# bue_steuerung.net
KiCad netlist of a schematic drawn in EAGLE
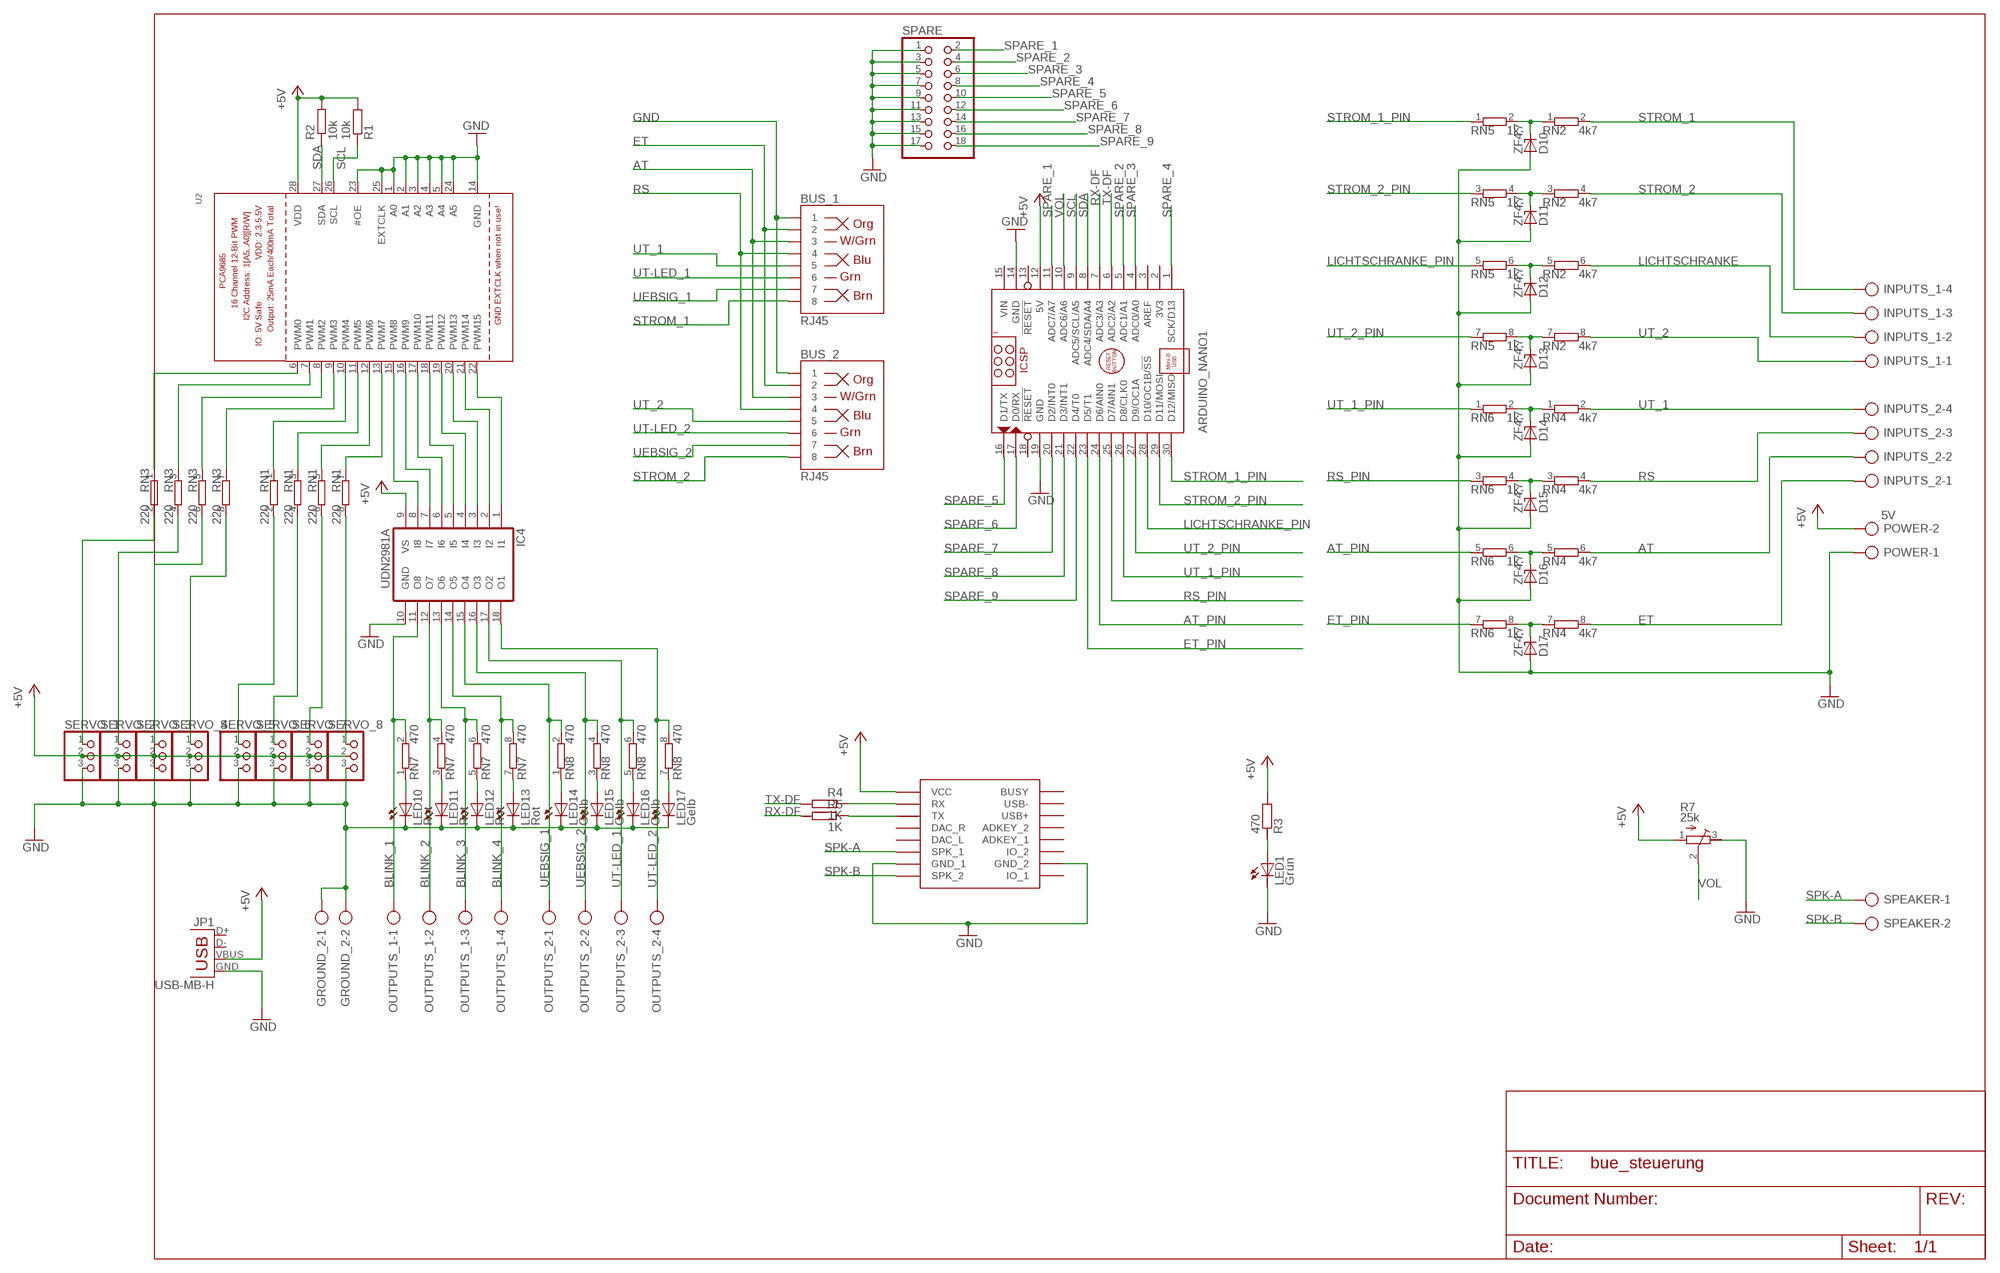
[diagram p0: schematic, sheet 1]

(export (version "E")
  (design (tool "Eeschema 10.0.6"))
  (components
    (comp (ref "ARDUINO_NANO1")
      (value "ARDUINO_NANO")
      (footprint "eagle-import:ARDUINO_NANO")
      (libsource (lib "eagle-import") (part "ARDUINO_NANO"))
    )
    (comp (ref "BUS_1")
      (value "RJ45")
      (footprint "eagle-import:RJ45-8")
      (libsource (lib "eagle-import") (part "RJ45-8PTH"))
    )
    (comp (ref "BUS_2")
      (value "RJ45")
      (footprint "eagle-import:RJ45-8")
      (libsource (lib "eagle-import") (part "RJ45-8PTH"))
    )
    (comp (ref "D10")
      (value "ZF4,7")
      (footprint "eagle-import:ZDIO-2.5")
      (libsource (lib "eagle-import") (part "ZENER-DIODEZD-2.5"))
    )
    (comp (ref "D11")
      (value "ZF4,7")
      (footprint "eagle-import:ZDIO-5")
      (libsource (lib "eagle-import") (part "ZENER-DIODEZD-5"))
    )
    (comp (ref "D12")
      (value "ZF4,7")
      (footprint "eagle-import:ZDIO-10")
      (libsource (lib "eagle-import") (part "ZENER-DIODEZD-10"))
    )
    (comp (ref "D13")
      (value "ZF4,7")
      (footprint "eagle-import:ZDIO12.5")
      (libsource (lib "eagle-import") (part "ZENER-DIODEZD-12.5"))
    )
    (comp (ref "D14")
      (value "ZF4,7")
      (footprint "eagle-import:ZDIO12.5")
      (libsource (lib "eagle-import") (part "ZENER-DIODEZD-12.5"))
    )
    (comp (ref "D15")
      (value "ZF4,7")
      (footprint "eagle-import:ZDIO-10")
      (libsource (lib "eagle-import") (part "ZENER-DIODEZD-10"))
    )
    (comp (ref "D16")
      (value "ZF4,7")
      (footprint "eagle-import:ZDIO-5")
      (libsource (lib "eagle-import") (part "ZENER-DIODEZD-5"))
    )
    (comp (ref "D17")
      (value "ZF4,7")
      (footprint "eagle-import:ZDIO-2.5")
      (libsource (lib "eagle-import") (part "ZENER-DIODEZD-2.5"))
    )
    (comp (ref "GROUND_2")
      (value "AK500/2")
      (footprint "eagle-import:AK500_2")
      (libsource (lib "eagle-import") (part "AK500/2"))
    )
    (comp (ref "IC4")
      (value "UDN2981A")
      (footprint "eagle-import:DIL18")
      (libsource (lib "eagle-import") (part "UDN298A1"))
    )
    (comp (ref "INPUTS_1")
      (value "AK500/4")
      (footprint "eagle-import:AK500_4")
      (libsource (lib "eagle-import") (part "AK500/4"))
    )
    (comp (ref "INPUTS_2")
      (value "AK500/4")
      (footprint "eagle-import:AK500_4")
      (libsource (lib "eagle-import") (part "AK500/4"))
    )
    (comp (ref "JP1")
      (value "USB-MB-H")
      (footprint "eagle-import:USB-MB-H")
      (libsource (lib "eagle-import") (part "USB-MB-H"))
    )
    (comp (ref "LED1")
      (value "Grün")
      (footprint "eagle-import:LED3MM")
      (libsource (lib "eagle-import") (part "LED3MM"))
    )
    (comp (ref "LED10")
      (value "Rot")
      (footprint "eagle-import:LED3MM")
      (libsource (lib "eagle-import") (part "LED3MM"))
    )
    (comp (ref "LED11")
      (value "Rot")
      (footprint "eagle-import:LED3MM")
      (libsource (lib "eagle-import") (part "LED3MM"))
    )
    (comp (ref "LED12")
      (value "Rot")
      (footprint "eagle-import:LED3MM")
      (libsource (lib "eagle-import") (part "LED3MM"))
    )
    (comp (ref "LED13")
      (value "Rot")
      (footprint "eagle-import:LED3MM")
      (libsource (lib "eagle-import") (part "LED3MM"))
    )
    (comp (ref "LED14")
      (value "Gelb")
      (footprint "eagle-import:LED3MM")
      (libsource (lib "eagle-import") (part "LED3MM"))
    )
    (comp (ref "LED15")
      (value "Gelb")
      (footprint "eagle-import:LED3MM")
      (libsource (lib "eagle-import") (part "LED3MM"))
    )
    (comp (ref "LED16")
      (value "Gelb")
      (footprint "eagle-import:LED3MM")
      (libsource (lib "eagle-import") (part "LED3MM"))
    )
    (comp (ref "LED17")
      (value "Gelb")
      (footprint "eagle-import:LED3MM")
      (libsource (lib "eagle-import") (part "LED3MM"))
    )
    (comp (ref "OUTPUTS_1")
      (value "AK500/4")
      (footprint "eagle-import:AK500_4")
      (libsource (lib "eagle-import") (part "AK500/4"))
    )
    (comp (ref "OUTPUTS_2")
      (value "AK500/4")
      (footprint "eagle-import:AK500_4")
      (libsource (lib "eagle-import") (part "AK500/4"))
    )
    (comp (ref "POWER")
      (value "5V")
      (footprint "eagle-import:AK500_2")
      (libsource (lib "eagle-import") (part "AK500/2"))
    )
    (comp (ref "R1")
      (value "10k")
      (footprint "eagle-import:0207_10")
      (libsource (lib "eagle-import") (part "R-EU_0207/10"))
    )
    (comp (ref "R2")
      (value "10k")
      (footprint "eagle-import:0207_10")
      (libsource (lib "eagle-import") (part "R-EU_0207/10"))
    )
    (comp (ref "R3")
      (value "470")
      (footprint "eagle-import:0207_10")
      (libsource (lib "eagle-import") (part "R-EU_0207/10"))
    )
    (comp (ref "R4")
      (value "1K")
      (footprint "eagle-import:0207_10")
      (libsource (lib "eagle-import") (part "R-EU_0207/10"))
    )
    (comp (ref "R5")
      (value "1K")
      (footprint "eagle-import:0207_10")
      (libsource (lib "eagle-import") (part "R-EU_0207/10"))
    )
    (comp (ref "R7")
      (value "25k")
      (footprint "eagle-import:RTRIM64Z")
      (libsource (lib "eagle-import") (part "R-TRIMM64Z"))
    )
    (comp (ref "RN1")
      (value "220")
      (footprint "eagle-import:SIL8")
      (libsource (lib "eagle-import") (part "E4RP"))
    )
    (comp (ref "RN2")
      (value "4k7")
      (footprint "eagle-import:SIL8")
      (libsource (lib "eagle-import") (part "E4RP"))
    )
    (comp (ref "RN3")
      (value "220")
      (footprint "eagle-import:SIL8")
      (libsource (lib "eagle-import") (part "E4RP"))
    )
    (comp (ref "RN4")
      (value "4k7")
      (footprint "eagle-import:SIL8")
      (libsource (lib "eagle-import") (part "E4RP"))
    )
    (comp (ref "RN5")
      (value "1k")
      (footprint "eagle-import:SIL8")
      (libsource (lib "eagle-import") (part "E4RP"))
    )
    (comp (ref "RN6")
      (value "1k")
      (footprint "eagle-import:SIL8")
      (libsource (lib "eagle-import") (part "E4RP"))
    )
    (comp (ref "RN7")
      (value "470")
      (footprint "eagle-import:SIL8")
      (libsource (lib "eagle-import") (part "E4RP"))
    )
    (comp (ref "RN8")
      (value "470")
      (footprint "eagle-import:SIL8")
      (libsource (lib "eagle-import") (part "E4RP"))
    )
    (comp (ref "SERVO_1")
      (value "PINHD-1X3")
      (footprint "eagle-import:1X03")
      (libsource (lib "eagle-import") (part "PINHD-1X3"))
    )
    (comp (ref "SERVO_2")
      (value "PINHD-1X3")
      (footprint "eagle-import:1X03")
      (libsource (lib "eagle-import") (part "PINHD-1X3"))
    )
    (comp (ref "SERVO_3")
      (value "PINHD-1X3")
      (footprint "eagle-import:1X03")
      (libsource (lib "eagle-import") (part "PINHD-1X3"))
    )
    (comp (ref "SERVO_4")
      (value "PINHD-1X3")
      (footprint "eagle-import:1X03")
      (libsource (lib "eagle-import") (part "PINHD-1X3"))
    )
    (comp (ref "SERVO_5")
      (value "PINHD-1X3")
      (footprint "eagle-import:1X03")
      (libsource (lib "eagle-import") (part "PINHD-1X3"))
    )
    (comp (ref "SERVO_6")
      (value "PINHD-1X3")
      (footprint "eagle-import:1X03")
      (libsource (lib "eagle-import") (part "PINHD-1X3"))
    )
    (comp (ref "SERVO_7")
      (value "PINHD-1X3")
      (footprint "eagle-import:1X03")
      (libsource (lib "eagle-import") (part "PINHD-1X3"))
    )
    (comp (ref "SERVO_8")
      (value "PINHD-1X3")
      (footprint "eagle-import:1X03")
      (libsource (lib "eagle-import") (part "PINHD-1X3"))
    )
    (comp (ref "SPARE")
      (value "PINHD-2X9")
      (footprint "eagle-import:2X09")
      (libsource (lib "eagle-import") (part "PINHD-2X9"))
    )
    (comp (ref "SPEAKER")
      (value "AK500/2")
      (footprint "eagle-import:AK500_2")
      (libsource (lib "eagle-import") (part "AK500/2"))
    )
    (comp (ref "U$1")
      (value "DFPLAYER")
      (footprint "eagle-import:DFPLAYER")
      (libsource (lib "eagle-import") (part "DFPLAYER"))
    )
    (comp (ref "U2")
      (value "PCA9685")
      (footprint "eagle-import:TSSOP28")
      (libsource (lib "eagle-import") (part "PCA9685"))
    )
  )
  (nets
    (net (code "1") (name "+5V") (class "Default")
      (node (ref "ARDUINO_NANO1") (pin "12") (pinfunction "5V_12") (pintype "power_in"))
      (node (ref "IC4") (pin "9") (pinfunction "VS_9") (pintype "passive"))
      (node (ref "JP1") (pin "VBUS") (pinfunction "VBUS_VBUS") (pintype "bidirectional"))
      (node (ref "POWER") (pin "2") (pinfunction "KL_2") (pintype "passive"))
      (node (ref "R1") (pin "2") (pinfunction "2_2") (pintype "passive"))
      (node (ref "R2") (pin "2") (pinfunction "2_2") (pintype "passive"))
      (node (ref "R3") (pin "2") (pinfunction "2_2") (pintype "passive"))
      (node (ref "R7") (pin "1") (pinfunction "E_1") (pintype "passive"))
      (node (ref "SERVO_1") (pin "2") (pinfunction "2_2") (pintype "passive"))
      (node (ref "SERVO_2") (pin "2") (pinfunction "2_2") (pintype "passive"))
      (node (ref "SERVO_3") (pin "2") (pinfunction "2_2") (pintype "passive"))
      (node (ref "SERVO_4") (pin "2") (pinfunction "2_2") (pintype "passive"))
      (node (ref "SERVO_5") (pin "2") (pinfunction "2_2") (pintype "passive"))
      (node (ref "SERVO_6") (pin "2") (pinfunction "2_2") (pintype "passive"))
      (node (ref "SERVO_7") (pin "2") (pinfunction "2_2") (pintype "passive"))
      (node (ref "SERVO_8") (pin "2") (pinfunction "2_2") (pintype "passive"))
      (node (ref "U$1") (pin "VCC") (pinfunction "VCC_VCC") (pintype "bidirectional"))
      (node (ref "U2") (pin "28") (pinfunction "VDD_28") (pintype "power_in"))
    )
    (net (code "2") (name "/AT") (class "Default")
      (node (ref "BUS_1") (pin "3") (pinfunction "3_3") (pintype "bidirectional"))
      (node (ref "BUS_2") (pin "3") (pinfunction "3_3") (pintype "bidirectional"))
      (node (ref "INPUTS_2") (pin "2") (pinfunction "KL_2") (pintype "passive"))
      (node (ref "RN4") (pin "6") (pinfunction "2_6") (pintype "passive"))
    )
    (net (code "3") (name "/AT_PIN") (class "Default")
      (node (ref "ARDUINO_NANO1") (pin "24") (pinfunction "D6/AIN0_24") (pintype "bidirectional"))
      (node (ref "RN6") (pin "5") (pinfunction "1_5") (pintype "passive"))
    )
    (net (code "4") (name "/BLINK_1") (class "Default")
      (node (ref "IC4") (pin "11") (pinfunction "O8_11") (pintype "open_collector"))
      (node (ref "OUTPUTS_1") (pin "1") (pinfunction "KL_1") (pintype "passive"))
      (node (ref "RN7") (pin "2") (pinfunction "2_2") (pintype "passive"))
    )
    (net (code "5") (name "/BLINK_2") (class "Default")
      (node (ref "IC4") (pin "12") (pinfunction "O7_12") (pintype "open_collector"))
      (node (ref "OUTPUTS_1") (pin "2") (pinfunction "KL_2") (pintype "passive"))
      (node (ref "RN7") (pin "4") (pinfunction "2_4") (pintype "passive"))
    )
    (net (code "6") (name "/BLINK_3") (class "Default")
      (node (ref "IC4") (pin "13") (pinfunction "O6_13") (pintype "open_collector"))
      (node (ref "OUTPUTS_1") (pin "3") (pinfunction "KL_3") (pintype "passive"))
      (node (ref "RN7") (pin "6") (pinfunction "2_6") (pintype "passive"))
    )
    (net (code "7") (name "/BLINK_4") (class "Default")
      (node (ref "IC4") (pin "14") (pinfunction "O5_14") (pintype "open_collector"))
      (node (ref "OUTPUTS_1") (pin "4") (pinfunction "KL_4") (pintype "passive"))
      (node (ref "RN7") (pin "8") (pinfunction "2_8") (pintype "passive"))
    )
    (net (code "8") (name "/ET") (class "Default")
      (node (ref "BUS_1") (pin "2") (pinfunction "2_2") (pintype "bidirectional"))
      (node (ref "BUS_2") (pin "2") (pinfunction "2_2") (pintype "bidirectional"))
      (node (ref "INPUTS_2") (pin "1") (pinfunction "KL_1") (pintype "passive"))
      (node (ref "RN4") (pin "8") (pinfunction "2_8") (pintype "passive"))
    )
    (net (code "9") (name "/ET_PIN") (class "Default")
      (node (ref "ARDUINO_NANO1") (pin "23") (pinfunction "D5/T1_23") (pintype "bidirectional"))
      (node (ref "RN6") (pin "7") (pinfunction "1_7") (pintype "passive"))
    )
    (net (code "10") (name "/LICHTSCHRANKE") (class "Default")
      (node (ref "INPUTS_1") (pin "2") (pinfunction "KL_2") (pintype "passive"))
      (node (ref "RN2") (pin "6") (pinfunction "2_6") (pintype "passive"))
    )
    (net (code "11") (name "/LICHTSCHRANKE_PIN") (class "Default")
      (node (ref "ARDUINO_NANO1") (pin "28") (pinfunction "D10/OC1B/~{SS}_28") (pintype "bidirectional"))
      (node (ref "RN5") (pin "5") (pinfunction "1_5") (pintype "passive"))
    )
    (net (code "12") (name "/RS") (class "Default")
      (node (ref "BUS_1") (pin "4") (pinfunction "4_4") (pintype "bidirectional"))
      (node (ref "BUS_2") (pin "4") (pinfunction "4_4") (pintype "bidirectional"))
      (node (ref "INPUTS_2") (pin "3") (pinfunction "KL_3") (pintype "passive"))
      (node (ref "RN4") (pin "4") (pinfunction "2_4") (pintype "passive"))
    )
    (net (code "13") (name "/RS_PIN") (class "Default")
      (node (ref "ARDUINO_NANO1") (pin "25") (pinfunction "D7/AIN1_25") (pintype "bidirectional"))
      (node (ref "RN6") (pin "3") (pinfunction "1_3") (pintype "passive"))
    )
    (net (code "14") (name "/RX-DF") (class "Default")
      (node (ref "ARDUINO_NANO1") (pin "7") (pinfunction "ADC3/A3_7") (pintype "bidirectional"))
      (node (ref "R5") (pin "2") (pinfunction "2_2") (pintype "passive"))
    )
    (net (code "15") (name "/SCL") (class "Default")
      (node (ref "ARDUINO_NANO1") (pin "9") (pinfunction "ADC5/SCL/A5_9") (pintype "bidirectional"))
      (node (ref "R1") (pin "1") (pinfunction "1_1") (pintype "passive"))
      (node (ref "U2") (pin "26") (pinfunction "SCL_26") (pintype "bidirectional"))
    )
    (net (code "16") (name "/SDA") (class "Default")
      (node (ref "ARDUINO_NANO1") (pin "8") (pinfunction "ADC4/SDA/A4_8") (pintype "bidirectional"))
      (node (ref "R2") (pin "1") (pinfunction "1_1") (pintype "passive"))
      (node (ref "U2") (pin "27") (pinfunction "SDA_27") (pintype "bidirectional"))
    )
    (net (code "17") (name "/SPARE_1") (class "Default")
      (node (ref "ARDUINO_NANO1") (pin "11") (pinfunction "ADC7/A7_11") (pintype "bidirectional"))
      (node (ref "SPARE") (pin "2") (pinfunction "2_2") (pintype "passive"))
    )
    (net (code "18") (name "/SPARE_2") (class "Default")
      (node (ref "ARDUINO_NANO1") (pin "5") (pinfunction "ADC1/A1_5") (pintype "bidirectional"))
      (node (ref "SPARE") (pin "4") (pinfunction "4_4") (pintype "passive"))
    )
    (net (code "19") (name "/SPARE_3") (class "Default")
      (node (ref "ARDUINO_NANO1") (pin "4") (pinfunction "ADC0/A0_4") (pintype "bidirectional"))
      (node (ref "SPARE") (pin "6") (pinfunction "6_6") (pintype "passive"))
    )
    (net (code "20") (name "/SPARE_4") (class "Default")
      (node (ref "ARDUINO_NANO1") (pin "1") (pinfunction "SCK/D13_1") (pintype "bidirectional"))
      (node (ref "SPARE") (pin "8") (pinfunction "8_8") (pintype "passive"))
    )
    (net (code "21") (name "/SPARE_5") (class "Default")
      (node (ref "ARDUINO_NANO1") (pin "16") (pinfunction "D1/TX_16") (pintype "bidirectional"))
      (node (ref "SPARE") (pin "10") (pinfunction "10_10") (pintype "passive"))
    )
    (net (code "22") (name "/SPARE_6") (class "Default")
      (node (ref "ARDUINO_NANO1") (pin "17") (pinfunction "D0/RX_17") (pintype "bidirectional"))
      (node (ref "SPARE") (pin "12") (pinfunction "12_12") (pintype "passive"))
    )
    (net (code "23") (name "/SPARE_7") (class "Default")
      (node (ref "ARDUINO_NANO1") (pin "20") (pinfunction "D2/INT0_20") (pintype "bidirectional"))
      (node (ref "SPARE") (pin "14") (pinfunction "14_14") (pintype "passive"))
    )
    (net (code "24") (name "/SPARE_8") (class "Default")
      (node (ref "ARDUINO_NANO1") (pin "21") (pinfunction "D3/INT1_21") (pintype "bidirectional"))
      (node (ref "SPARE") (pin "16") (pinfunction "16_16") (pintype "passive"))
    )
    (net (code "25") (name "/SPARE_9") (class "Default")
      (node (ref "ARDUINO_NANO1") (pin "22") (pinfunction "D4/T0_22") (pintype "bidirectional"))
      (node (ref "SPARE") (pin "18") (pinfunction "18_18") (pintype "passive"))
    )
    (net (code "26") (name "/SPK-A") (class "Default")
      (node (ref "SPEAKER") (pin "1") (pinfunction "KL_1") (pintype "passive"))
      (node (ref "U$1") (pin "SPK1") (pinfunction "SPK_1_SPK1") (pintype "bidirectional"))
    )
    (net (code "27") (name "/SPK-B") (class "Default")
      (node (ref "SPEAKER") (pin "2") (pinfunction "KL_2") (pintype "passive"))
      (node (ref "U$1") (pin "SPK2") (pinfunction "SPK_2_SPK2") (pintype "bidirectional"))
    )
    (net (code "28") (name "/STROM_1") (class "Default")
      (node (ref "BUS_1") (pin "8") (pinfunction "8_8") (pintype "bidirectional"))
      (node (ref "INPUTS_1") (pin "4") (pinfunction "KL_4") (pintype "passive"))
      (node (ref "RN2") (pin "2") (pinfunction "2_2") (pintype "passive"))
    )
    (net (code "29") (name "/STROM_1_PIN") (class "Default")
      (node (ref "ARDUINO_NANO1") (pin "30") (pinfunction "D12/MISO_30") (pintype "bidirectional"))
      (node (ref "RN5") (pin "1") (pinfunction "1_1") (pintype "passive"))
    )
    (net (code "30") (name "/STROM_2") (class "Default")
      (node (ref "BUS_2") (pin "8") (pinfunction "8_8") (pintype "bidirectional"))
      (node (ref "INPUTS_1") (pin "3") (pinfunction "KL_3") (pintype "passive"))
      (node (ref "RN2") (pin "4") (pinfunction "2_4") (pintype "passive"))
    )
    (net (code "31") (name "/STROM_2_PIN") (class "Default")
      (node (ref "ARDUINO_NANO1") (pin "29") (pinfunction "D11/MOSI_29") (pintype "bidirectional"))
      (node (ref "RN5") (pin "3") (pinfunction "1_3") (pintype "passive"))
    )
    (net (code "32") (name "/TX-DF") (class "Default")
      (node (ref "ARDUINO_NANO1") (pin "6") (pinfunction "ADC2/A2_6") (pintype "bidirectional"))
      (node (ref "R4") (pin "2") (pinfunction "2_2") (pintype "passive"))
    )
    (net (code "33") (name "/UEBSIG_1") (class "Default")
      (node (ref "BUS_1") (pin "7") (pinfunction "7_7") (pintype "bidirectional"))
      (node (ref "IC4") (pin "15") (pinfunction "O4_15") (pintype "open_collector"))
      (node (ref "OUTPUTS_2") (pin "1") (pinfunction "KL_1") (pintype "passive"))
      (node (ref "RN8") (pin "2") (pinfunction "2_2") (pintype "passive"))
    )
    (net (code "34") (name "/UEBSIG_2") (class "Default")
      (node (ref "BUS_2") (pin "7") (pinfunction "7_7") (pintype "bidirectional"))
      (node (ref "IC4") (pin "16") (pinfunction "O3_16") (pintype "open_collector"))
      (node (ref "OUTPUTS_2") (pin "2") (pinfunction "KL_2") (pintype "passive"))
      (node (ref "RN8") (pin "4") (pinfunction "2_4") (pintype "passive"))
    )
    (net (code "35") (name "/UT-LED_1") (class "Default")
      (node (ref "BUS_1") (pin "6") (pinfunction "6_6") (pintype "bidirectional"))
      (node (ref "IC4") (pin "17") (pinfunction "O2_17") (pintype "open_collector"))
      (node (ref "OUTPUTS_2") (pin "3") (pinfunction "KL_3") (pintype "passive"))
      (node (ref "RN8") (pin "6") (pinfunction "2_6") (pintype "passive"))
    )
    (net (code "36") (name "/UT-LED_2") (class "Default")
      (node (ref "BUS_2") (pin "6") (pinfunction "6_6") (pintype "bidirectional"))
      (node (ref "IC4") (pin "18") (pinfunction "O1_18") (pintype "open_collector"))
      (node (ref "OUTPUTS_2") (pin "4") (pinfunction "KL_4") (pintype "passive"))
      (node (ref "RN8") (pin "8") (pinfunction "2_8") (pintype "passive"))
    )
    (net (code "37") (name "/UT_1") (class "Default")
      (node (ref "BUS_1") (pin "5") (pinfunction "5_5") (pintype "bidirectional"))
      (node (ref "INPUTS_2") (pin "4") (pinfunction "KL_4") (pintype "passive"))
      (node (ref "RN4") (pin "2") (pinfunction "2_2") (pintype "passive"))
    )
    (net (code "38") (name "/UT_1_PIN") (class "Default")
      (node (ref "ARDUINO_NANO1") (pin "26") (pinfunction "D8/CLK0_26") (pintype "bidirectional"))
      (node (ref "RN6") (pin "1") (pinfunction "1_1") (pintype "passive"))
    )
    (net (code "39") (name "/UT_2") (class "Default")
      (node (ref "BUS_2") (pin "5") (pinfunction "5_5") (pintype "bidirectional"))
      (node (ref "INPUTS_1") (pin "1") (pinfunction "KL_1") (pintype "passive"))
      (node (ref "RN2") (pin "8") (pinfunction "2_8") (pintype "passive"))
    )
    (net (code "40") (name "/UT_2_PIN") (class "Default")
      (node (ref "ARDUINO_NANO1") (pin "27") (pinfunction "D9/OC1A_27") (pintype "bidirectional"))
      (node (ref "RN5") (pin "7") (pinfunction "1_7") (pintype "passive"))
    )
    (net (code "41") (name "/VIN") (class "Default")
      (node (ref "ARDUINO_NANO1") (pin "15") (pinfunction "VIN_15") (pintype "power_in"))
    )
    (net (code "42") (name "/VOL") (class "Default")
      (node (ref "ARDUINO_NANO1") (pin "10") (pinfunction "ADC6/A6_10") (pintype "bidirectional"))
      (node (ref "R7") (pin "2") (pinfunction "S_2") (pintype "passive"))
    )
    (net (code "43") (name "GND") (class "Default")
      (node (ref "ARDUINO_NANO1") (pin "14") (pinfunction "GND_14") (pintype "power_in"))
      (node (ref "ARDUINO_NANO1") (pin "19") (pinfunction "GND_19") (pintype "power_in"))
      (node (ref "BUS_1") (pin "1") (pinfunction "1_1") (pintype "bidirectional"))
      (node (ref "BUS_2") (pin "1") (pinfunction "1_1") (pintype "bidirectional"))
      (node (ref "D10") (pin "A") (pinfunction "A_A") (pintype "passive"))
      (node (ref "D11") (pin "A") (pinfunction "A_A") (pintype "passive"))
      (node (ref "D12") (pin "A") (pinfunction "A_A") (pintype "passive"))
      (node (ref "D13") (pin "A") (pinfunction "A_A") (pintype "passive"))
      (node (ref "D14") (pin "A") (pinfunction "A_A") (pintype "passive"))
      (node (ref "D15") (pin "A") (pinfunction "A_A") (pintype "passive"))
      (node (ref "D16") (pin "A") (pinfunction "A_A") (pintype "passive"))
      (node (ref "D17") (pin "A") (pinfunction "A_A") (pintype "passive"))
      (node (ref "GROUND_2") (pin "1") (pinfunction "KL_1") (pintype "passive"))
      (node (ref "GROUND_2") (pin "2") (pinfunction "KL_2") (pintype "passive"))
      (node (ref "IC4") (pin "10") (pinfunction "GND_10") (pintype "power_in"))
      (node (ref "JP1") (pin "GND") (pinfunction "GND_GND") (pintype "bidirectional"))
      (node (ref "LED1") (pin "K") (pinfunction "C_K") (pintype "passive"))
      (node (ref "LED10") (pin "K") (pinfunction "C_K") (pintype "passive"))
      (node (ref "LED11") (pin "K") (pinfunction "C_K") (pintype "passive"))
      (node (ref "LED12") (pin "K") (pinfunction "C_K") (pintype "passive"))
      (node (ref "LED13") (pin "K") (pinfunction "C_K") (pintype "passive"))
      (node (ref "LED14") (pin "K") (pinfunction "C_K") (pintype "passive"))
      (node (ref "LED15") (pin "K") (pinfunction "C_K") (pintype "passive"))
      (node (ref "LED16") (pin "K") (pinfunction "C_K") (pintype "passive"))
      (node (ref "LED17") (pin "K") (pinfunction "C_K") (pintype "passive"))
      (node (ref "POWER") (pin "1") (pinfunction "KL_1") (pintype "passive"))
      (node (ref "R7") (pin "3") (pinfunction "A_3") (pintype "passive"))
      (node (ref "SERVO_1") (pin "3") (pinfunction "3_3") (pintype "passive"))
      (node (ref "SERVO_2") (pin "3") (pinfunction "3_3") (pintype "passive"))
      (node (ref "SERVO_3") (pin "3") (pinfunction "3_3") (pintype "passive"))
      (node (ref "SERVO_4") (pin "3") (pinfunction "3_3") (pintype "passive"))
      (node (ref "SERVO_5") (pin "3") (pinfunction "3_3") (pintype "passive"))
      (node (ref "SERVO_6") (pin "3") (pinfunction "3_3") (pintype "passive"))
      (node (ref "SERVO_7") (pin "3") (pinfunction "3_3") (pintype "passive"))
      (node (ref "SERVO_8") (pin "3") (pinfunction "3_3") (pintype "passive"))
      (node (ref "SPARE") (pin "1") (pinfunction "1_1") (pintype "passive"))
      (node (ref "SPARE") (pin "11") (pinfunction "11_11") (pintype "passive"))
      (node (ref "SPARE") (pin "13") (pinfunction "13_13") (pintype "passive"))
      (node (ref "SPARE") (pin "15") (pinfunction "15_15") (pintype "passive"))
      (node (ref "SPARE") (pin "17") (pinfunction "17_17") (pintype "passive"))
      (node (ref "SPARE") (pin "3") (pinfunction "3_3") (pintype "passive"))
      (node (ref "SPARE") (pin "5") (pinfunction "5_5") (pintype "passive"))
      (node (ref "SPARE") (pin "7") (pinfunction "7_7") (pintype "passive"))
      (node (ref "SPARE") (pin "9") (pinfunction "9_9") (pintype "passive"))
      (node (ref "U$1") (pin "GND_1") (pinfunction "GND_1_GND_1") (pintype "bidirectional"))
      (node (ref "U$1") (pin "GND_2") (pinfunction "GND_2_GND_2") (pintype "bidirectional"))
      (node (ref "U2") (pin "1") (pinfunction "A0_1") (pintype "bidirectional"))
      (node (ref "U2") (pin "14") (pinfunction "GND_14") (pintype "power_in"))
      (node (ref "U2") (pin "2") (pinfunction "A1_2") (pintype "bidirectional"))
      (node (ref "U2") (pin "23") (pinfunction "#OE_23") (pintype "input"))
      (node (ref "U2") (pin "24") (pinfunction "A5_24") (pintype "bidirectional"))
      (node (ref "U2") (pin "25") (pinfunction "EXTCLK_25") (pintype "input"))
      (node (ref "U2") (pin "3") (pinfunction "A2_3") (pintype "bidirectional"))
      (node (ref "U2") (pin "4") (pinfunction "A3_4") (pintype "bidirectional"))
      (node (ref "U2") (pin "5") (pinfunction "A4_5") (pintype "bidirectional"))
    )
    (net (code "44") (name "Net-(D10-PadC)") (class "Default")
      (node (ref "D10") (pin "C") (pinfunction "C_C") (pintype "passive"))
      (node (ref "RN2") (pin "1") (pinfunction "1_1") (pintype "passive"))
      (node (ref "RN5") (pin "2") (pinfunction "2_2") (pintype "passive"))
    )
    (net (code "45") (name "Net-(D14-PadC)") (class "Default")
      (node (ref "D14") (pin "C") (pinfunction "C_C") (pintype "passive"))
      (node (ref "RN4") (pin "1") (pinfunction "1_1") (pintype "passive"))
      (node (ref "RN6") (pin "2") (pinfunction "2_2") (pintype "passive"))
    )
    (net (code "46") (name "Net-(IC4-I1)") (class "Default")
      (node (ref "IC4") (pin "1") (pinfunction "I1_1") (pintype "input"))
      (node (ref "U2") (pin "22") (pinfunction "PWM15_22") (pintype "output"))
    )
    (net (code "47") (name "Net-(IC4-I2)") (class "Default")
      (node (ref "IC4") (pin "2") (pinfunction "I2_2") (pintype "input"))
      (node (ref "U2") (pin "21") (pinfunction "PWM14_21") (pintype "output"))
    )
    (net (code "48") (name "Net-(IC4-I3)") (class "Default")
      (node (ref "IC4") (pin "3") (pinfunction "I3_3") (pintype "input"))
      (node (ref "U2") (pin "20") (pinfunction "PWM13_20") (pintype "output"))
    )
    (net (code "49") (name "Net-(IC4-I4)") (class "Default")
      (node (ref "IC4") (pin "4") (pinfunction "I4_4") (pintype "input"))
      (node (ref "U2") (pin "19") (pinfunction "PWM12_19") (pintype "output"))
    )
    (net (code "50") (name "Net-(IC4-I5)") (class "Default")
      (node (ref "IC4") (pin "5") (pinfunction "I5_5") (pintype "input"))
      (node (ref "U2") (pin "18") (pinfunction "PWM11_18") (pintype "output"))
    )
    (net (code "51") (name "Net-(IC4-I6)") (class "Default")
      (node (ref "IC4") (pin "6") (pinfunction "I6_6") (pintype "input"))
      (node (ref "U2") (pin "17") (pinfunction "PWM10_17") (pintype "output"))
    )
    (net (code "52") (name "Net-(IC4-I7)") (class "Default")
      (node (ref "IC4") (pin "7") (pinfunction "I7_7") (pintype "input"))
      (node (ref "U2") (pin "16") (pinfunction "PWM9_16") (pintype "output"))
    )
    (net (code "53") (name "Net-(IC4-I8)") (class "Default")
      (node (ref "IC4") (pin "8") (pinfunction "I8_8") (pintype "input"))
      (node (ref "U2") (pin "15") (pinfunction "PWM8_15") (pintype "output"))
    )
    (net (code "54") (name "Net-(LED1-PadA)") (class "Default")
      (node (ref "LED1") (pin "A") (pinfunction "A_A") (pintype "passive"))
      (node (ref "R3") (pin "1") (pinfunction "1_1") (pintype "passive"))
    )
    (net (code "55") (name "Net-(LED10-PadA)") (class "Default")
      (node (ref "LED10") (pin "A") (pinfunction "A_A") (pintype "passive"))
      (node (ref "RN7") (pin "1") (pinfunction "1_1") (pintype "passive"))
    )
    (net (code "56") (name "Net-(LED14-PadA)") (class "Default")
      (node (ref "LED14") (pin "A") (pinfunction "A_A") (pintype "passive"))
      (node (ref "RN8") (pin "1") (pinfunction "1_1") (pintype "passive"))
    )
    (net (code "57") (name "Net-(R4-Pad1)") (class "Default")
      (node (ref "R4") (pin "1") (pinfunction "1_1") (pintype "passive"))
      (node (ref "U$1") (pin "RX") (pinfunction "RX_RX") (pintype "bidirectional"))
    )
    (net (code "58") (name "Net-(R5-Pad1)") (class "Default")
      (node (ref "R5") (pin "1") (pinfunction "1_1") (pintype "passive"))
      (node (ref "U$1") (pin "TX") (pinfunction "TX_TX") (pintype "bidirectional"))
    )
    (net (code "59") (name "Net-(RN1-Pad2)") (class "Default")
      (node (ref "RN1") (pin "2") (pinfunction "2_2") (pintype "passive"))
      (node (ref "SERVO_5") (pin "1") (pinfunction "1_1") (pintype "passive"))
    )
    (net (code "60") (name "Net-(RN1B-1)") (class "Default")
      (node (ref "RN1") (pin "3") (pinfunction "1_3") (pintype "passive"))
      (node (ref "U2") (pin "11") (pinfunction "PWM5_11") (pintype "output"))
    )
    (net (code "61") (name "Net-(RN1B-2)") (class "Default")
      (node (ref "RN1") (pin "4") (pinfunction "2_4") (pintype "passive"))
      (node (ref "SERVO_6") (pin "1") (pinfunction "1_1") (pintype "passive"))
    )
    (net (code "62") (name "Net-(RN1C-1)") (class "Default")
      (node (ref "RN1") (pin "5") (pinfunction "1_5") (pintype "passive"))
      (node (ref "U2") (pin "12") (pinfunction "PWM6_12") (pintype "output"))
    )
    (net (code "63") (name "Net-(RN1C-2)") (class "Default")
      (node (ref "RN1") (pin "6") (pinfunction "2_6") (pintype "passive"))
      (node (ref "SERVO_7") (pin "1") (pinfunction "1_1") (pintype "passive"))
    )
    (net (code "64") (name "Net-(RN1D-1)") (class "Default")
      (node (ref "RN1") (pin "7") (pinfunction "1_7") (pintype "passive"))
      (node (ref "U2") (pin "13") (pinfunction "PWM7_13") (pintype "output"))
    )
    (net (code "65") (name "Net-(RN1D-2)") (class "Default")
      (node (ref "RN1") (pin "8") (pinfunction "2_8") (pintype "passive"))
      (node (ref "SERVO_8") (pin "1") (pinfunction "1_1") (pintype "passive"))
    )
    (net (code "66") (name "Net-(RN2B-1)") (class "Default")
      (node (ref "D11") (pin "C") (pinfunction "C_C") (pintype "passive"))
      (node (ref "RN2") (pin "3") (pinfunction "1_3") (pintype "passive"))
      (node (ref "RN5") (pin "4") (pinfunction "2_4") (pintype "passive"))
    )
    (net (code "67") (name "Net-(RN2C-1)") (class "Default")
      (node (ref "D12") (pin "C") (pinfunction "C_C") (pintype "passive"))
      (node (ref "RN2") (pin "5") (pinfunction "1_5") (pintype "passive"))
      (node (ref "RN5") (pin "6") (pinfunction "2_6") (pintype "passive"))
    )
    (net (code "68") (name "Net-(RN2D-1)") (class "Default")
      (node (ref "D13") (pin "C") (pinfunction "C_C") (pintype "passive"))
      (node (ref "RN2") (pin "7") (pinfunction "1_7") (pintype "passive"))
      (node (ref "RN5") (pin "8") (pinfunction "2_8") (pintype "passive"))
    )
    (net (code "69") (name "Net-(RN3-Pad2)") (class "Default")
      (node (ref "RN3") (pin "2") (pinfunction "2_2") (pintype "passive"))
      (node (ref "SERVO_1") (pin "1") (pinfunction "1_1") (pintype "passive"))
    )
    (net (code "70") (name "Net-(RN3B-1)") (class "Default")
      (node (ref "RN3") (pin "3") (pinfunction "1_3") (pintype "passive"))
      (node (ref "U2") (pin "7") (pinfunction "PWM1_7") (pintype "output"))
    )
    (net (code "71") (name "Net-(RN3B-2)") (class "Default")
      (node (ref "RN3") (pin "4") (pinfunction "2_4") (pintype "passive"))
      (node (ref "SERVO_2") (pin "1") (pinfunction "1_1") (pintype "passive"))
    )
    (net (code "72") (name "Net-(RN3C-1)") (class "Default")
      (node (ref "RN3") (pin "5") (pinfunction "1_5") (pintype "passive"))
      (node (ref "U2") (pin "8") (pinfunction "PWM2_8") (pintype "output"))
    )
    (net (code "73") (name "Net-(RN3C-2)") (class "Default")
      (node (ref "RN3") (pin "6") (pinfunction "2_6") (pintype "passive"))
      (node (ref "SERVO_3") (pin "1") (pinfunction "1_1") (pintype "passive"))
    )
    (net (code "74") (name "Net-(RN3D-1)") (class "Default")
      (node (ref "RN3") (pin "7") (pinfunction "1_7") (pintype "passive"))
      (node (ref "U2") (pin "9") (pinfunction "PWM3_9") (pintype "output"))
    )
    (net (code "75") (name "Net-(RN3D-2)") (class "Default")
      (node (ref "RN3") (pin "8") (pinfunction "2_8") (pintype "passive"))
      (node (ref "SERVO_4") (pin "1") (pinfunction "1_1") (pintype "passive"))
    )
    (net (code "76") (name "Net-(RN4B-1)") (class "Default")
      (node (ref "D15") (pin "C") (pinfunction "C_C") (pintype "passive"))
      (node (ref "RN4") (pin "3") (pinfunction "1_3") (pintype "passive"))
      (node (ref "RN6") (pin "4") (pinfunction "2_4") (pintype "passive"))
    )
    (net (code "77") (name "Net-(RN4C-1)") (class "Default")
      (node (ref "D16") (pin "C") (pinfunction "C_C") (pintype "passive"))
      (node (ref "RN4") (pin "5") (pinfunction "1_5") (pintype "passive"))
      (node (ref "RN6") (pin "6") (pinfunction "2_6") (pintype "passive"))
    )
    (net (code "78") (name "Net-(RN4D-1)") (class "Default")
      (node (ref "D17") (pin "C") (pinfunction "C_C") (pintype "passive"))
      (node (ref "RN4") (pin "7") (pinfunction "1_7") (pintype "passive"))
      (node (ref "RN6") (pin "8") (pinfunction "2_8") (pintype "passive"))
    )
    (net (code "79") (name "Net-(RN7B-1)") (class "Default")
      (node (ref "LED11") (pin "A") (pinfunction "A_A") (pintype "passive"))
      (node (ref "RN7") (pin "3") (pinfunction "1_3") (pintype "passive"))
    )
    (net (code "80") (name "Net-(RN7C-1)") (class "Default")
      (node (ref "LED12") (pin "A") (pinfunction "A_A") (pintype "passive"))
      (node (ref "RN7") (pin "5") (pinfunction "1_5") (pintype "passive"))
    )
    (net (code "81") (name "Net-(RN7D-1)") (class "Default")
      (node (ref "LED13") (pin "A") (pinfunction "A_A") (pintype "passive"))
      (node (ref "RN7") (pin "7") (pinfunction "1_7") (pintype "passive"))
    )
    (net (code "82") (name "Net-(RN8B-1)") (class "Default")
      (node (ref "LED15") (pin "A") (pinfunction "A_A") (pintype "passive"))
      (node (ref "RN8") (pin "3") (pinfunction "1_3") (pintype "passive"))
    )
    (net (code "83") (name "Net-(RN8C-1)") (class "Default")
      (node (ref "LED16") (pin "A") (pinfunction "A_A") (pintype "passive"))
      (node (ref "RN8") (pin "5") (pinfunction "1_5") (pintype "passive"))
    )
    (net (code "84") (name "Net-(RN8D-1)") (class "Default")
      (node (ref "LED17") (pin "A") (pinfunction "A_A") (pintype "passive"))
      (node (ref "RN8") (pin "7") (pinfunction "1_7") (pintype "passive"))
    )
    (net (code "85") (name "Net-(U2-PWM0)") (class "Default")
      (node (ref "RN3") (pin "1") (pinfunction "1_1") (pintype "passive"))
      (node (ref "U2") (pin "6") (pinfunction "PWM0_6") (pintype "output"))
    )
    (net (code "86") (name "Net-(U2-PWM4)") (class "Default")
      (node (ref "RN1") (pin "1") (pinfunction "1_1") (pintype "passive"))
      (node (ref "U2") (pin "10") (pinfunction "PWM4_10") (pintype "output"))
    )
    (net (code "87") (name "unconnected-(ARDUINO_NANO1-3V3-Pad2)") (class "Default")
      (node (ref "ARDUINO_NANO1") (pin "2") (pinfunction "3V3_2") (pintype "output"))
    )
    (net (code "88") (name "unconnected-(ARDUINO_NANO1-AREF-Pad3)") (class "Default")
      (node (ref "ARDUINO_NANO1") (pin "3") (pinfunction "AREF_3") (pintype "input"))
    )
    (net (code "89") (name "unconnected-(ARDUINO_NANO1-~{RESET}-Pad13)") (class "Default")
      (node (ref "ARDUINO_NANO1") (pin "13") (pinfunction "~{RESET}_13") (pintype "input"))
    )
    (net (code "90") (name "unconnected-(ARDUINO_NANO1-~{RESET}-Pad18)") (class "Default")
      (node (ref "ARDUINO_NANO1") (pin "18") (pinfunction "~{RESET}_18") (pintype "input"))
    )
    (net (code "91") (name "unconnected-(JP1-PadD+)") (class "Default")
      (node (ref "JP1") (pin "D+") (pinfunction "D+_D+") (pintype "bidirectional"))
    )
    (net (code "92") (name "unconnected-(JP1-PadD-)") (class "Default")
      (node (ref "JP1") (pin "D-") (pinfunction "D-_D-") (pintype "bidirectional"))
    )
    (net (code "93") (name "unconnected-(U$1-ADKEY_1-PadADKEY1)") (class "Default")
      (node (ref "U$1") (pin "ADKEY1") (pinfunction "ADKEY_1_ADKEY1") (pintype "bidirectional"))
    )
    (net (code "94") (name "unconnected-(U$1-ADKEY_2-PadADKEY2)") (class "Default")
      (node (ref "U$1") (pin "ADKEY2") (pinfunction "ADKEY_2_ADKEY2") (pintype "bidirectional"))
    )
    (net (code "95") (name "unconnected-(U$1-IO_1-PadIO1)") (class "Default")
      (node (ref "U$1") (pin "IO1") (pinfunction "IO_1_IO1") (pintype "bidirectional"))
    )
    (net (code "96") (name "unconnected-(U$1-IO_2-PadIO2)") (class "Default")
      (node (ref "U$1") (pin "IO2") (pinfunction "IO_2_IO2") (pintype "bidirectional"))
    )
    (net (code "97") (name "unconnected-(U$1-PadBUSY)") (class "Default")
      (node (ref "U$1") (pin "BUSY") (pinfunction "BUSY_BUSY") (pintype "bidirectional"))
    )
    (net (code "98") (name "unconnected-(U$1-PadDAC_L)") (class "Default")
      (node (ref "U$1") (pin "DAC_L") (pinfunction "DAC_L_DAC_L") (pintype "bidirectional"))
    )
    (net (code "99") (name "unconnected-(U$1-PadDAC_R)") (class "Default")
      (node (ref "U$1") (pin "DAC_R") (pinfunction "DAC_R_DAC_R") (pintype "bidirectional"))
    )
    (net (code "100") (name "unconnected-(U$1-PadUSB+)") (class "Default")
      (node (ref "U$1") (pin "USB+") (pinfunction "USB+_USB+") (pintype "bidirectional"))
    )
    (net (code "101") (name "unconnected-(U$1-PadUSB-)") (class "Default")
      (node (ref "U$1") (pin "USB-") (pinfunction "USB-_USB-") (pintype "bidirectional"))
    )
  )
)
